# VHF_AMP.net
KiCad netlist of a schematic drawn in Altium Designer
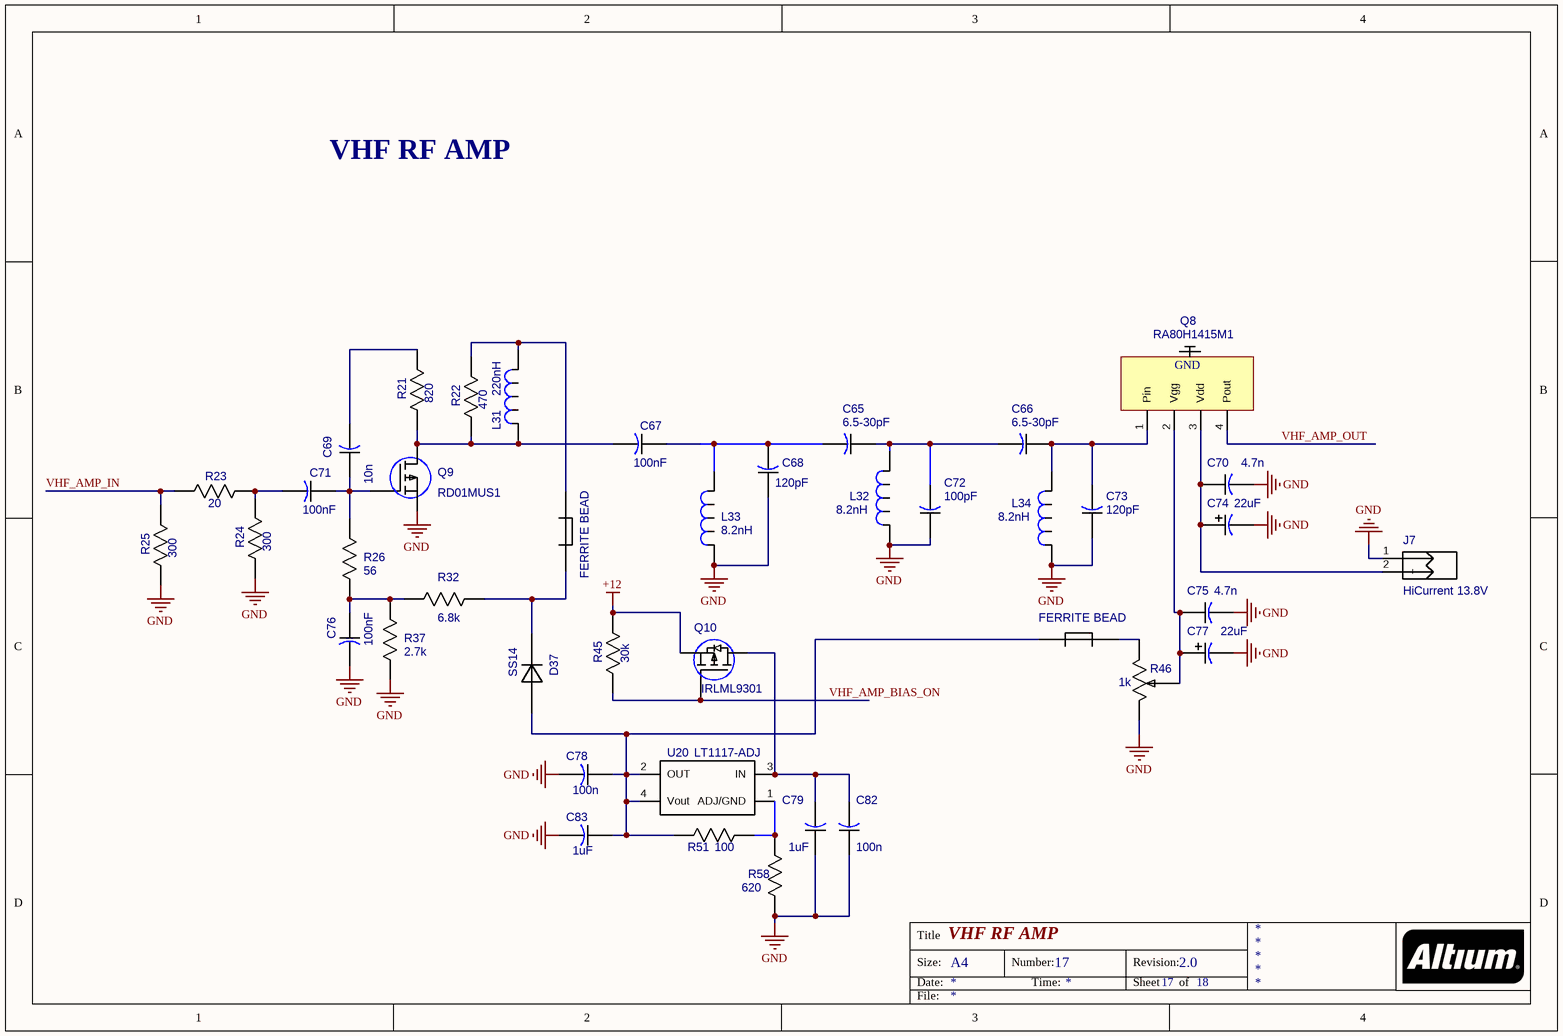
[diagram p0: VHF_AMP.SchDoc]

(export (version "E")
  (design (tool "Eeschema 10.0.6"))
  (components
    (comp (ref "C65")
      (value "6.5-30pF")
      (footprint "5025[2010]")
      (description "TZC3P300A110")
      (libsource (lib "*") (part "CAP_0805"))
    )
    (comp (ref "C66")
      (value "6.5-30pF")
      (footprint "5025[2010]")
      (description "TZC3P300A110")
      (libsource (lib "*") (part "CAP_0805"))
    )
    (comp (ref "C67")
      (value "100nF")
      (footprint "CAP_0805")
      (description "CAP_0805")
      (libsource (lib "*") (part "CAP_0805"))
    )
    (comp (ref "C68")
      (value "120pF")
      (footprint "CAP_0805")
      (description "CAP_0805")
      (libsource (lib "*") (part "CAP_0805"))
    )
    (comp (ref "C69")
      (value "10n")
      (footprint "CAP_1206")
      (description "CAP_1206")
      (libsource (lib "*") (part "CAP_1206"))
    )
    (comp (ref "C70")
      (value "4.7n")
      (footprint "CAP_0805")
      (description "CAP_0805")
      (libsource (lib "*") (part "CAP_0805"))
    )
    (comp (ref "C71")
      (value "100nF")
      (footprint "CAP_0805")
      (description "CAP_0805")
      (libsource (lib "*") (part "CAP_0805"))
    )
    (comp (ref "C72")
      (value "100pF")
      (footprint "CAP_0805")
      (description "CAP_0805")
      (libsource (lib "*") (part "CAP_0805"))
    )
    (comp (ref "C73")
      (value "120pF")
      (footprint "CAP_0805")
      (description "CAP_0805")
      (libsource (lib "*") (part "CAP_0805"))
    )
    (comp (ref "C74")
      (value "22uF")
      (footprint "CAPAE_6.6x6.6h5.4")
      (description "CAPAE_6.6x6.6h5.4")
      (libsource (lib "*") (part "CAPAE_6.6x6.6h5.4"))
    )
    (comp (ref "C75")
      (value "4.7n")
      (footprint "CAP_0805")
      (description "CAP_0805")
      (libsource (lib "*") (part "CAP_0805"))
    )
    (comp (ref "C76")
      (value "100nF")
      (footprint "CAP_0805")
      (description "CAP_0805")
      (libsource (lib "*") (part "CAP_0805"))
    )
    (comp (ref "C77")
      (value "22uF")
      (footprint "CAPAE_6.6x6.6h5.4")
      (description "CAPAE_6.6x6.6h5.4")
      (libsource (lib "*") (part "CAPAE_6.6x6.6h5.4"))
    )
    (comp (ref "C78")
      (value "100n")
      (footprint "CAP_0805")
      (description "CAP_0805")
      (libsource (lib "*") (part "CAP_0805"))
    )
    (comp (ref "C79")
      (value "1uF")
      (footprint "CAP_0805")
      (description "CAP_0805")
      (libsource (lib "*") (part "CAP_0805"))
    )
    (comp (ref "C82")
      (value "100n")
      (footprint "CAP_0805")
      (description "CAP_0805")
      (libsource (lib "*") (part "CAP_0805"))
    )
    (comp (ref "C83")
      (value "1uF")
      (footprint "CAP_0805")
      (description "CAP_0805")
      (libsource (lib "*") (part "CAP_0805"))
    )
    (comp (ref "D37") (value "SS14") (footprint "SS14") (libsource (lib "*") (part "SS14")))
    (comp (ref "F1")
      (value "FERRITE BEAD")
      (footprint "RES")
      (description "IND_FERRITE_BEAD")
      (libsource (lib "RF-UNIT-BIG") (part "IND_FERRITE_BEAD"))
    )
    (comp (ref "F2")
      (value "FERRITE BEAD")
      (footprint "RES")
      (description "IND_FERRITE_BEAD")
      (libsource (lib "RF-UNIT-BIG") (part "IND_FERRITE_BEAD"))
    )
    (comp (ref "J7")
      (value "HiCurrent 13.8V")
      (footprint "1986717-2")
      (description "JX2")
      (libsource (lib "*") (part "1986717-2"))
    )
    (comp (ref "L31")
      (value "220nH")
      (footprint "IND_1206")
      (description "IND_1206")
      (fields (field (name "Comment") "10uH"))
      (libsource (lib "*") (part "IND_1206"))
    )
    (comp (ref "L32")
      (value "8.2nH")
      (footprint "IND_0805")
      (description "IND_0805")
      (libsource (lib "*") (part "IND_0805"))
    )
    (comp (ref "L33")
      (value "8.2nH")
      (footprint "IND_0805")
      (description "IND_0805")
      (libsource (lib "*") (part "IND_0805"))
    )
    (comp (ref "L34")
      (value "8.2nH")
      (footprint "IND_0805")
      (description "IND_0805")
      (libsource (lib "*") (part "IND_0805"))
    )
    (comp (ref "Q8")
      (value "RA80H1415M1")
      (footprint "RA80H1415M1")
      (libsource (lib "RF-UNIT-BIG") (part "RA80H1415M1"))
    )
    (comp (ref "Q9") (value "RD01MUS1") (footprint "SOT89") (libsource (lib "RF-UNIT-BIG") (part "RD01MUS1")))
    (comp (ref "Q10")
      (value "IRLML9301")
      (footprint "SOT23")
      (description "MOSFET")
      (libsource (lib "*") (part "MOSFET_ENH_PD"))
    )
    (comp (ref "R21")
      (value "820")
      (footprint "RES_1206")
      (description "RES_1206")
      (libsource (lib "*") (part "RES_1206"))
    )
    (comp (ref "R22")
      (value "470")
      (footprint "RES_1206")
      (description "RES_1206")
      (libsource (lib "*") (part "RES_1206"))
    )
    (comp (ref "R23")
      (value "20")
      (footprint "RES_1206")
      (description "RES_1206")
      (libsource (lib "*") (part "RES_1206"))
    )
    (comp (ref "R24")
      (value "300")
      (footprint "RES_1206")
      (description "RES_1206")
      (libsource (lib "*") (part "RES_1206"))
    )
    (comp (ref "R25")
      (value "300")
      (footprint "RES_1206")
      (description "RES_1206")
      (libsource (lib "*") (part "RES_1206"))
    )
    (comp (ref "R26")
      (value "56")
      (footprint "RES_0805")
      (description "RES_0805")
      (libsource (lib "*") (part "RES_0805"))
    )
    (comp (ref "R32")
      (value "6.8k")
      (footprint "RES_0805")
      (description "RES_0805")
      (libsource (lib "*") (part "RES_0805"))
    )
    (comp (ref "R37")
      (value "2.7k")
      (footprint "RES_0805")
      (description "RES_0805")
      (libsource (lib "*") (part "RES_0805"))
    )
    (comp (ref "R45")
      (value "30k")
      (footprint "RES_0805")
      (description "RES_0805")
      (libsource (lib "*") (part "RES_0805"))
    )
    (comp (ref "R46")
      (value "1k")
      (footprint "306J")
      (description "306J")
      (fields (field (name "Comment") "ADJ-1k"))
      (libsource (lib "*") (part "306J"))
    )
    (comp (ref "R51")
      (value "100")
      (footprint "RES_0805")
      (description "RES_0805")
      (libsource (lib "*") (part "RES_0805"))
    )
    (comp (ref "R58")
      (value "620")
      (footprint "RES_0805")
      (description "RES_0805")
      (libsource (lib "*") (part "RES_0805"))
    )
    (comp (ref "U20")
      (value "LT1117-ADJ")
      (footprint "LT1117IST-ADJ")
      (description "LT1117IST-ADJ")
      (libsource (lib "*") (part "LT1117IST-ADJ"))
    )
  )
  (nets
    (net (code "1") (name "+12") (class "Default")
      (node (ref "Q10") (pin "2") (pinfunction "S_2") (pintype "passive"))
      (node (ref "R45") (pin "2") (pinfunction "2_2") (pintype "passive"))
    )
    (net (code "2") (name "/VHF_AMP_BIAS_ON") (class "Default")
      (node (ref "Q10") (pin "1") (pinfunction "G_1") (pintype "passive"))
      (node (ref "R45") (pin "1") (pinfunction "1_1") (pintype "passive"))
    )
    (net (code "3") (name "/VHF_AMP_IN") (class "Default")
      (node (ref "R23") (pin "1") (pinfunction "1_1") (pintype "passive"))
      (node (ref "R25") (pin "2") (pinfunction "2_2") (pintype "passive"))
    )
    (net (code "4") (name "/VHF_AMP_OUT") (class "Default")
      (node (ref "Q8") (pin "4") (pinfunction "Pout_4") (pintype "passive"))
    )
    (net (code "5") (name "GND") (class "Default")
      (node (ref "C68") (pin "1") (pinfunction "1_1") (pintype "passive"))
      (node (ref "C70") (pin "2") (pinfunction "2_2") (pintype "passive"))
      (node (ref "C72") (pin "1") (pinfunction "1_1") (pintype "passive"))
      (node (ref "C73") (pin "1") (pinfunction "1_1") (pintype "passive"))
      (node (ref "C74") (pin "2") (pinfunction "MINUS_2") (pintype "passive"))
      (node (ref "C75") (pin "2") (pinfunction "2_2") (pintype "passive"))
      (node (ref "C76") (pin "2") (pinfunction "2_2") (pintype "passive"))
      (node (ref "C77") (pin "2") (pinfunction "MINUS_2") (pintype "passive"))
      (node (ref "C78") (pin "2") (pinfunction "2_2") (pintype "passive"))
      (node (ref "C79") (pin "1") (pinfunction "1_1") (pintype "passive"))
      (node (ref "C82") (pin "1") (pinfunction "1_1") (pintype "passive"))
      (node (ref "C83") (pin "2") (pinfunction "2_2") (pintype "passive"))
      (node (ref "J7") (pin "1") (pinfunction "-_1") (pintype "passive"))
      (node (ref "L32") (pin "1") (pinfunction "1_1") (pintype "passive"))
      (node (ref "L33") (pin "1") (pinfunction "1_1") (pintype "passive"))
      (node (ref "L34") (pin "1") (pinfunction "1_1") (pintype "passive"))
      (node (ref "Q9") (pin "2") (pinfunction "S_2") (pintype "passive"))
      (node (ref "R24") (pin "1") (pinfunction "1_1") (pintype "passive"))
      (node (ref "R25") (pin "1") (pinfunction "1_1") (pintype "passive"))
      (node (ref "R37") (pin "1") (pinfunction "1_1") (pintype "passive"))
      (node (ref "R46") (pin "1") (pinfunction "CCW_1") (pintype "passive"))
      (node (ref "R58") (pin "2") (pinfunction "2_2") (pintype "passive"))
    )
    (net (code "6") (name "Net-(C65-Pad1)") (class "Default")
      (node (ref "C65") (pin "1") (pinfunction "1_1") (pintype "passive"))
      (node (ref "C66") (pin "2") (pinfunction "2_2") (pintype "passive"))
      (node (ref "C72") (pin "2") (pinfunction "2_2") (pintype "passive"))
      (node (ref "L32") (pin "2") (pinfunction "2_2") (pintype "passive"))
    )
    (net (code "7") (name "Net-(C65-Pad2)") (class "Default")
      (node (ref "C65") (pin "2") (pinfunction "2_2") (pintype "passive"))
      (node (ref "C67") (pin "1") (pinfunction "1_1") (pintype "passive"))
      (node (ref "C68") (pin "2") (pinfunction "2_2") (pintype "passive"))
      (node (ref "L33") (pin "2") (pinfunction "2_2") (pintype "passive"))
    )
    (net (code "8") (name "Net-(C69-Pad2)") (class "Default")
      (node (ref "C69") (pin "2") (pinfunction "2_2") (pintype "passive"))
      (node (ref "R21") (pin "2") (pinfunction "2_2") (pintype "passive"))
    )
    (net (code "9") (name "Net-(C71-Pad2)") (class "Default")
      (node (ref "C71") (pin "2") (pinfunction "2_2") (pintype "passive"))
      (node (ref "R23") (pin "2") (pinfunction "2_2") (pintype "passive"))
      (node (ref "R24") (pin "2") (pinfunction "2_2") (pintype "passive"))
    )
    (net (code "10") (name "Net-(C74-PLUS)") (class "Default")
      (node (ref "C70") (pin "1") (pinfunction "1_1") (pintype "passive"))
      (node (ref "C74") (pin "1") (pinfunction "PLUS_1") (pintype "passive"))
      (node (ref "J7") (pin "2") (pinfunction "+_2") (pintype "passive"))
      (node (ref "Q8") (pin "3") (pinfunction "Vdd_3") (pintype "passive"))
    )
    (net (code "11") (name "Net-(C76-Pad1)") (class "Default")
      (node (ref "C76") (pin "1") (pinfunction "1_1") (pintype "passive"))
      (node (ref "R26") (pin "1") (pinfunction "1_1") (pintype "passive"))
      (node (ref "R32") (pin "2") (pinfunction "2_2") (pintype "passive"))
      (node (ref "R37") (pin "2") (pinfunction "2_2") (pintype "passive"))
    )
    (net (code "12") (name "Net-(C77-PLUS)") (class "Default")
      (node (ref "C75") (pin "1") (pinfunction "1_1") (pintype "passive"))
      (node (ref "C77") (pin "1") (pinfunction "PLUS_1") (pintype "passive"))
      (node (ref "Q8") (pin "2") (pinfunction "Vgg_2") (pintype "passive"))
      (node (ref "R46") (pin "2") (pinfunction "W_2") (pintype "passive"))
    )
    (net (code "13") (name "Net-(D37-A)") (class "Default")
      (node (ref "C78") (pin "1") (pinfunction "1_1") (pintype "passive"))
      (node (ref "C83") (pin "1") (pinfunction "1_1") (pintype "passive"))
      (node (ref "D37") (pin "2") (pinfunction "A_2") (pintype "passive"))
      (node (ref "F2") (pin "1") (pinfunction "1_1") (pintype "passive"))
      (node (ref "R51") (pin "1") (pinfunction "1_1") (pintype "passive"))
      (node (ref "U20") (pin "2") (pinfunction "OUT_2") (pintype "passive"))
      (node (ref "U20") (pin "4") (pinfunction "Vout_4") (pintype "passive"))
    )
    (net (code "14") (name "Net-(D37-K)") (class "Default")
      (node (ref "D37") (pin "1") (pinfunction "K_1") (pintype "passive"))
      (node (ref "F1") (pin "2") (pinfunction "2_2") (pintype "passive"))
      (node (ref "R32") (pin "1") (pinfunction "1_1") (pintype "passive"))
    )
    (net (code "15") (name "Net-(L31-1)") (class "Default")
      (node (ref "C67") (pin "2") (pinfunction "2_2") (pintype "passive"))
      (node (ref "L31") (pin "2") (pinfunction "1_2") (pintype "passive"))
      (node (ref "Q9") (pin "3") (pinfunction "D_3") (pintype "passive"))
      (node (ref "R21") (pin "1") (pinfunction "1_1") (pintype "passive"))
      (node (ref "R22") (pin "1") (pinfunction "1_1") (pintype "passive"))
    )
    (net (code "16") (name "Net-(L31-2)") (class "Default")
      (node (ref "F1") (pin "1") (pinfunction "1_1") (pintype "passive"))
      (node (ref "L31") (pin "1") (pinfunction "2_1") (pintype "passive"))
      (node (ref "R22") (pin "2") (pinfunction "2_2") (pintype "passive"))
    )
    (net (code "17") (name "Net-(Q8-Pin)") (class "Default")
      (node (ref "C66") (pin "1") (pinfunction "1_1") (pintype "passive"))
      (node (ref "C73") (pin "2") (pinfunction "2_2") (pintype "passive"))
      (node (ref "L34") (pin "2") (pinfunction "2_2") (pintype "passive"))
      (node (ref "Q8") (pin "1") (pinfunction "Pin_1") (pintype "passive"))
    )
    (net (code "18") (name "Net-(Q9-G)") (class "Default")
      (node (ref "C69") (pin "1") (pinfunction "1_1") (pintype "passive"))
      (node (ref "C71") (pin "1") (pinfunction "1_1") (pintype "passive"))
      (node (ref "Q9") (pin "1") (pinfunction "G_1") (pintype "passive"))
      (node (ref "R26") (pin "2") (pinfunction "2_2") (pintype "passive"))
    )
    (net (code "19") (name "Net-(Q10-D)") (class "Default")
      (node (ref "C79") (pin "2") (pinfunction "2_2") (pintype "passive"))
      (node (ref "C82") (pin "2") (pinfunction "2_2") (pintype "passive"))
      (node (ref "Q10") (pin "3") (pinfunction "D_3") (pintype "passive"))
      (node (ref "U20") (pin "3") (pinfunction "IN_3") (pintype "passive"))
    )
    (net (code "20") (name "Net-(R46-CW)") (class "Default")
      (node (ref "F2") (pin "2") (pinfunction "2_2") (pintype "passive"))
      (node (ref "R46") (pin "3") (pinfunction "CW_3") (pintype "passive"))
    )
    (net (code "21") (name "Net-(U20-ADJ{slash}GND)") (class "Default")
      (node (ref "R51") (pin "2") (pinfunction "2_2") (pintype "passive"))
      (node (ref "R58") (pin "1") (pinfunction "1_1") (pintype "passive"))
      (node (ref "U20") (pin "1") (pinfunction "ADJ/GND_1") (pintype "passive"))
    )
  )
)
